# DIRECTIONAL_COUPLER.net
KiCad netlist of a schematic drawn in Altium Designer
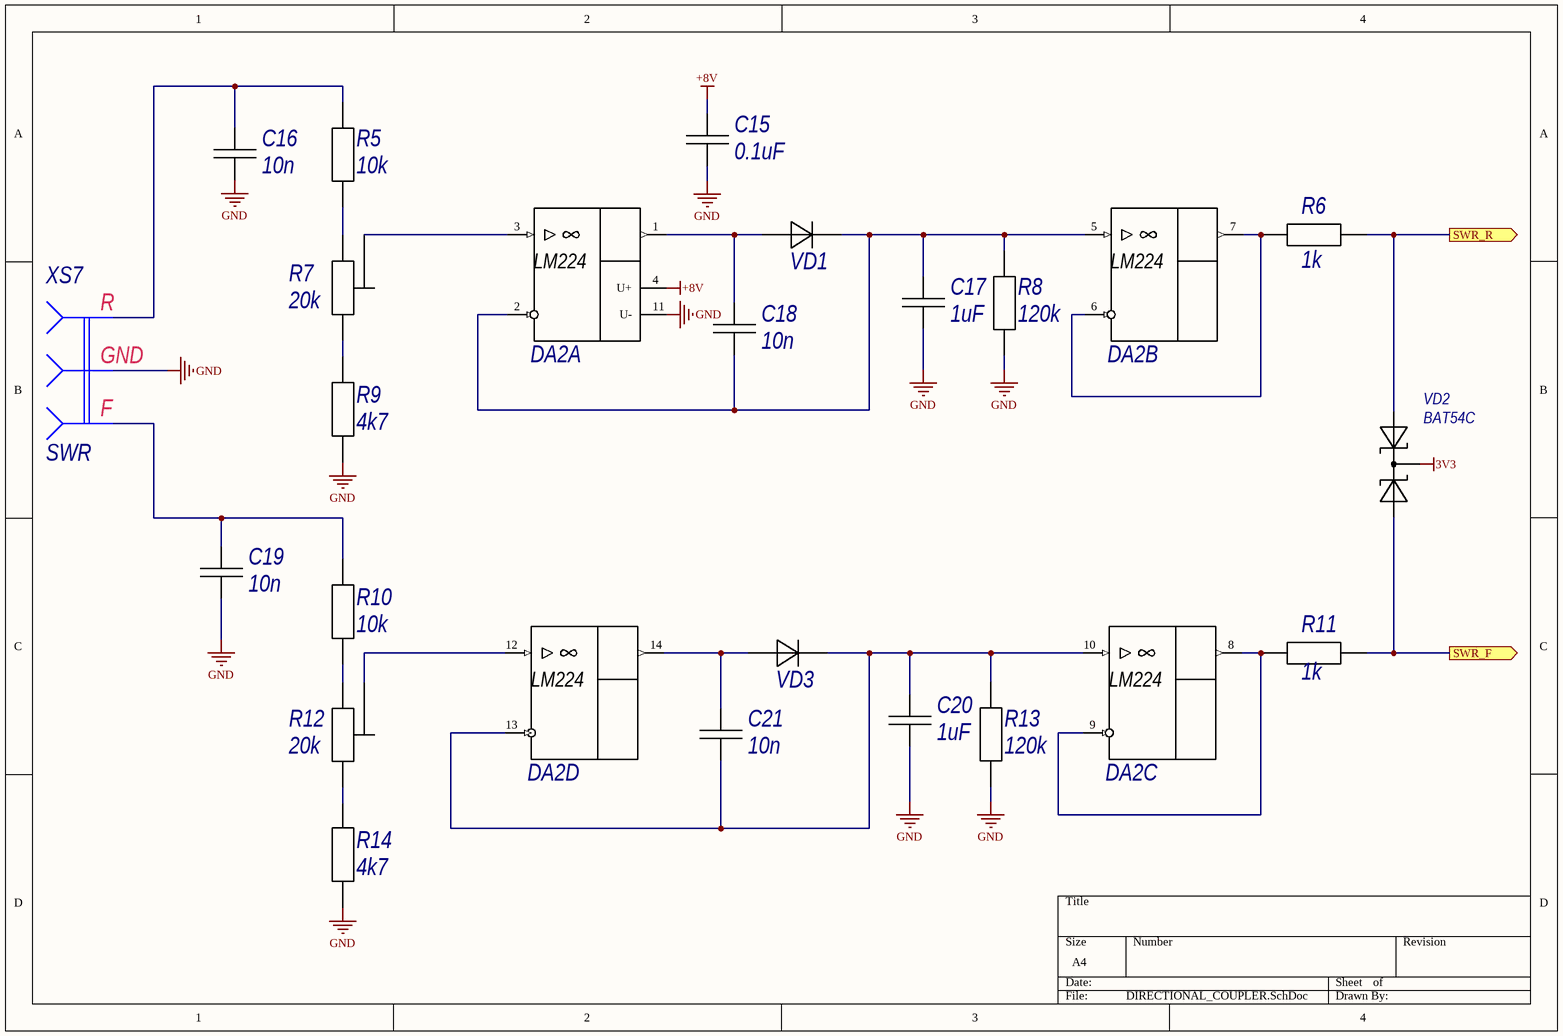
[diagram p0: DIRECTIONAL_COUPLER.SchDoc]

(export (version "E")
  (design (tool "Eeschema 10.0.6"))
  (components
    (comp (ref "C15")
      (value "0.1uF")
      (footprint "C0805C")
      (fields (field (name "PUBLISHER") "Andrew Danich"))
      (libsource (lib "PA_control_board") (part "CAP_0805"))
    )
    (comp (ref "C16")
      (value "10n")
      (footprint "C0805C")
      (fields (field (name "PUBLISHER") "Andrew Danich"))
      (libsource (lib "PA_control_board") (part "CAP_0805"))
    )
    (comp (ref "C17")
      (value "1uF")
      (footprint "C0805C")
      (fields (field (name "PUBLISHER") "Andrew Danich"))
      (libsource (lib "PA_control_board") (part "CAP_0805"))
    )
    (comp (ref "C18")
      (value "10n")
      (footprint "C0805C")
      (fields (field (name "PUBLISHER") "Andrew Danich"))
      (libsource (lib "PA_control_board") (part "CAP_0805"))
    )
    (comp (ref "C19")
      (value "10n")
      (footprint "C0805C")
      (fields (field (name "PUBLISHER") "Andrew Danich"))
      (libsource (lib "PA_control_board") (part "CAP_0805"))
    )
    (comp (ref "C20")
      (value "1uF")
      (footprint "C0805C")
      (fields (field (name "PUBLISHER") "Andrew Danich"))
      (libsource (lib "PA_control_board") (part "CAP_0805"))
    )
    (comp (ref "C21")
      (value "10n")
      (footprint "C0805C")
      (fields (field (name "PUBLISHER") "Andrew Danich"))
      (libsource (lib "PA_control_board") (part "CAP_0805"))
    )
    (comp (ref "DA2")
      (value "LM224")
      (footprint "Texas_Instruments_D0014A_IPC_A")
      (fields (field (name "PUBLISHER") "Andrew Danich"))
      (libsource (lib "PA_control_board") (part "LM224"))
    )
    (comp (ref "R5")
      (value "10k")
      (footprint "C0805R")
      (fields (field (name "PUBLISHER") "Andrew Danich"))
      (libsource (lib "PA_control_board") (part "RES_0805"))
    )
    (comp (ref "R6")
      (value "1k")
      (footprint "C0805R")
      (fields (field (name "PUBLISHER") "Andrew Danich"))
      (libsource (lib "PA_control_board") (part "RES_0805"))
    )
    (comp (ref "R7")
      (value "20k")
      (footprint "TRIM_3296W-1-254LF")
      (fields (field (name "PUBLISHER") "Andrew Danich"))
      (libsource (lib "PA_control_board") (part "Resistor-Trimmer-1"))
    )
    (comp (ref "R8")
      (value "120k")
      (footprint "C0805R")
      (fields (field (name "PUBLISHER") "Andrew Danich"))
      (libsource (lib "PA_control_board") (part "RES_0805"))
    )
    (comp (ref "R9")
      (value "4k7")
      (footprint "C0805R")
      (fields (field (name "PUBLISHER") "Andrew Danich"))
      (libsource (lib "PA_control_board") (part "RES_0805"))
    )
    (comp (ref "R10")
      (value "10k")
      (footprint "C0805R")
      (fields (field (name "PUBLISHER") "Andrew Danich"))
      (libsource (lib "PA_control_board") (part "RES_0805"))
    )
    (comp (ref "R11")
      (value "1k")
      (footprint "C0805R")
      (fields (field (name "PUBLISHER") "Andrew Danich"))
      (libsource (lib "PA_control_board") (part "RES_0805"))
    )
    (comp (ref "R12")
      (value "20k")
      (footprint "TRIM_3296W-1-254LF")
      (fields (field (name "PUBLISHER") "Andrew Danich"))
      (libsource (lib "PA_control_board") (part "Resistor-Trimmer-1"))
    )
    (comp (ref "R13")
      (value "120k")
      (footprint "C0805R")
      (fields (field (name "PUBLISHER") "Andrew Danich"))
      (libsource (lib "PA_control_board") (part "RES_0805"))
    )
    (comp (ref "R14")
      (value "4k7")
      (footprint "C0805R")
      (fields (field (name "PUBLISHER") "Andrew Danich"))
      (libsource (lib "PA_control_board") (part "RES_0805"))
    )
    (comp (ref "VD1")
      (value "LL4148")
      (footprint "DIO_LL4148")
      (fields (field (name "PUBLISHER") "Andrew Danich"))
      (libsource (lib "PA_control_board") (part "LL4148"))
    )
    (comp (ref "VD2")
      (value "BAT54C")
      (footprint "BAT54C_SOT23-3")
      (description "Small Signal Schottky Diode, Dual Common Cathode, 30 V, 200 mA, 400 mV, 600 mA, 125 C")
      (libsource (lib "PA_control_board") (part "BAT54C"))
    )
    (comp (ref "VD3")
      (value "LL4148")
      (footprint "DIO_LL4148")
      (fields (field (name "PUBLISHER") "Andrew Danich"))
      (libsource (lib "PA_control_board") (part "LL4148"))
    )
    (comp (ref "XS7")
      (value "SWR")
      (footprint "YX-XH-3")
      (fields (field (name "PUBLISHER") "Andrew Danich"))
      (libsource (lib "PA_control_board") (part "DIR_COUP"))
    )
  )
  (nets
    (net (code "1") (name "+8V") (class "Default")
      (node (ref "C15") (pin "2") (pinfunction "2_2") (pintype "passive"))
      (node (ref "DA2") (pin "4") (pinfunction "U+_4") (pintype "power_in"))
    )
    (net (code "2") (name "/SWR_F") (class "Default")
      (node (ref "R11") (pin "1") (pinfunction "1_1") (pintype "passive"))
      (node (ref "VD2") (pin "2") (pinfunction "C_2") (pintype "passive"))
    )
    (net (code "3") (name "/SWR_R") (class "Default")
      (node (ref "R6") (pin "1") (pinfunction "1_1") (pintype "passive"))
      (node (ref "VD2") (pin "1") (pinfunction "А1_1") (pintype "passive"))
    )
    (net (code "4") (name "3V3") (class "Default")
      (node (ref "VD2") (pin "3") (pinfunction "AC_3") (pintype "passive"))
    )
    (net (code "5") (name "GND") (class "Default")
      (node (ref "C15") (pin "1") (pinfunction "1_1") (pintype "passive"))
      (node (ref "C16") (pin "1") (pinfunction "1_1") (pintype "passive"))
      (node (ref "C17") (pin "1") (pinfunction "1_1") (pintype "passive"))
      (node (ref "C19") (pin "1") (pinfunction "1_1") (pintype "passive"))
      (node (ref "C20") (pin "1") (pinfunction "1_1") (pintype "passive"))
      (node (ref "DA2") (pin "11") (pinfunction "U-_11") (pintype "power_in"))
      (node (ref "R13") (pin "1") (pinfunction "1_1") (pintype "passive"))
      (node (ref "R14") (pin "1") (pinfunction "1_1") (pintype "passive"))
      (node (ref "R8") (pin "2") (pinfunction "2_2") (pintype "passive"))
      (node (ref "R9") (pin "1") (pinfunction "1_1") (pintype "passive"))
      (node (ref "XS7") (pin "2") (pintype "passive"))
    )
    (net (code "6") (name "Net-(C16-Pad2)") (class "Default")
      (node (ref "C16") (pin "2") (pinfunction "2_2") (pintype "passive"))
      (node (ref "R5") (pin "2") (pinfunction "2_2") (pintype "passive"))
      (node (ref "XS7") (pin "1") (pintype "passive"))
    )
    (net (code "7") (name "Net-(C19-Pad2)") (class "Default")
      (node (ref "C19") (pin "2") (pinfunction "2_2") (pintype "passive"))
      (node (ref "R10") (pin "2") (pinfunction "2_2") (pintype "passive"))
      (node (ref "XS7") (pin "3") (pintype "passive"))
    )
    (net (code "8") (name "Net-(DA2A-IN+)") (class "Default")
      (node (ref "DA2") (pin "3") (pinfunction "IN+_3") (pintype "input"))
      (node (ref "R7") (pin "2") (pinfunction "2_2") (pintype "passive"))
    )
    (net (code "9") (name "Net-(DA2A-IN-)") (class "Default")
      (node (ref "C17") (pin "2") (pinfunction "2_2") (pintype "passive"))
      (node (ref "C18") (pin "1") (pinfunction "1_1") (pintype "passive"))
      (node (ref "DA2") (pin "2") (pinfunction "IN-_2") (pintype "input"))
      (node (ref "DA2") (pin "5") (pinfunction "IN+_5") (pintype "input"))
      (node (ref "R8") (pin "1") (pinfunction "1_1") (pintype "passive"))
      (node (ref "VD1") (pin "2") (pinfunction "К_2") (pintype "passive"))
    )
    (net (code "10") (name "Net-(DA2A-OUT)") (class "Default")
      (node (ref "C18") (pin "2") (pinfunction "2_2") (pintype "passive"))
      (node (ref "DA2") (pin "1") (pinfunction "OUT_1") (pintype "output"))
      (node (ref "VD1") (pin "1") (pinfunction "А_1") (pintype "passive"))
    )
    (net (code "11") (name "Net-(DA2B-IN-)") (class "Default")
      (node (ref "DA2") (pin "6") (pinfunction "IN-_6") (pintype "input"))
      (node (ref "DA2") (pin "7") (pinfunction "OUT_7") (pintype "output"))
      (node (ref "R6") (pin "2") (pinfunction "2_2") (pintype "passive"))
    )
    (net (code "12") (name "Net-(DA2C-IN+)") (class "Default")
      (node (ref "C20") (pin "2") (pinfunction "2_2") (pintype "passive"))
      (node (ref "C21") (pin "1") (pinfunction "1_1") (pintype "passive"))
      (node (ref "DA2") (pin "10") (pinfunction "IN+_10") (pintype "input"))
      (node (ref "DA2") (pin "13") (pinfunction "IN-_13") (pintype "input"))
      (node (ref "R13") (pin "2") (pinfunction "2_2") (pintype "passive"))
      (node (ref "VD3") (pin "2") (pinfunction "К_2") (pintype "passive"))
    )
    (net (code "13") (name "Net-(DA2C-IN-)") (class "Default")
      (node (ref "DA2") (pin "8") (pinfunction "OUT_8") (pintype "output"))
      (node (ref "DA2") (pin "9") (pinfunction "IN-_9") (pintype "input"))
      (node (ref "R11") (pin "2") (pinfunction "2_2") (pintype "passive"))
    )
    (net (code "14") (name "Net-(DA2D-IN+)") (class "Default")
      (node (ref "DA2") (pin "12") (pinfunction "IN+_12") (pintype "input"))
      (node (ref "R12") (pin "2") (pinfunction "2_2") (pintype "passive"))
    )
    (net (code "15") (name "Net-(DA2D-OUT)") (class "Default")
      (node (ref "C21") (pin "2") (pinfunction "2_2") (pintype "passive"))
      (node (ref "DA2") (pin "14") (pinfunction "OUT_14") (pintype "output"))
      (node (ref "VD3") (pin "1") (pinfunction "А_1") (pintype "passive"))
    )
    (net (code "16") (name "Net-(R5-Pad1)") (class "Default")
      (node (ref "R5") (pin "1") (pinfunction "1_1") (pintype "passive"))
      (node (ref "R7") (pin "1") (pinfunction "1_1") (pintype "passive"))
    )
    (net (code "17") (name "Net-(R7-Pad3)") (class "Default")
      (node (ref "R7") (pin "3") (pinfunction "3_3") (pintype "passive"))
      (node (ref "R9") (pin "2") (pinfunction "2_2") (pintype "passive"))
    )
    (net (code "18") (name "Net-(R10-Pad1)") (class "Default")
      (node (ref "R10") (pin "1") (pinfunction "1_1") (pintype "passive"))
      (node (ref "R12") (pin "1") (pinfunction "1_1") (pintype "passive"))
    )
    (net (code "19") (name "Net-(R12-Pad3)") (class "Default")
      (node (ref "R12") (pin "3") (pinfunction "3_3") (pintype "passive"))
      (node (ref "R14") (pin "2") (pinfunction "2_2") (pintype "passive"))
    )
  )
)
